# SensorBreakout.net
KiCad netlist of a schematic drawn in Altium Designer
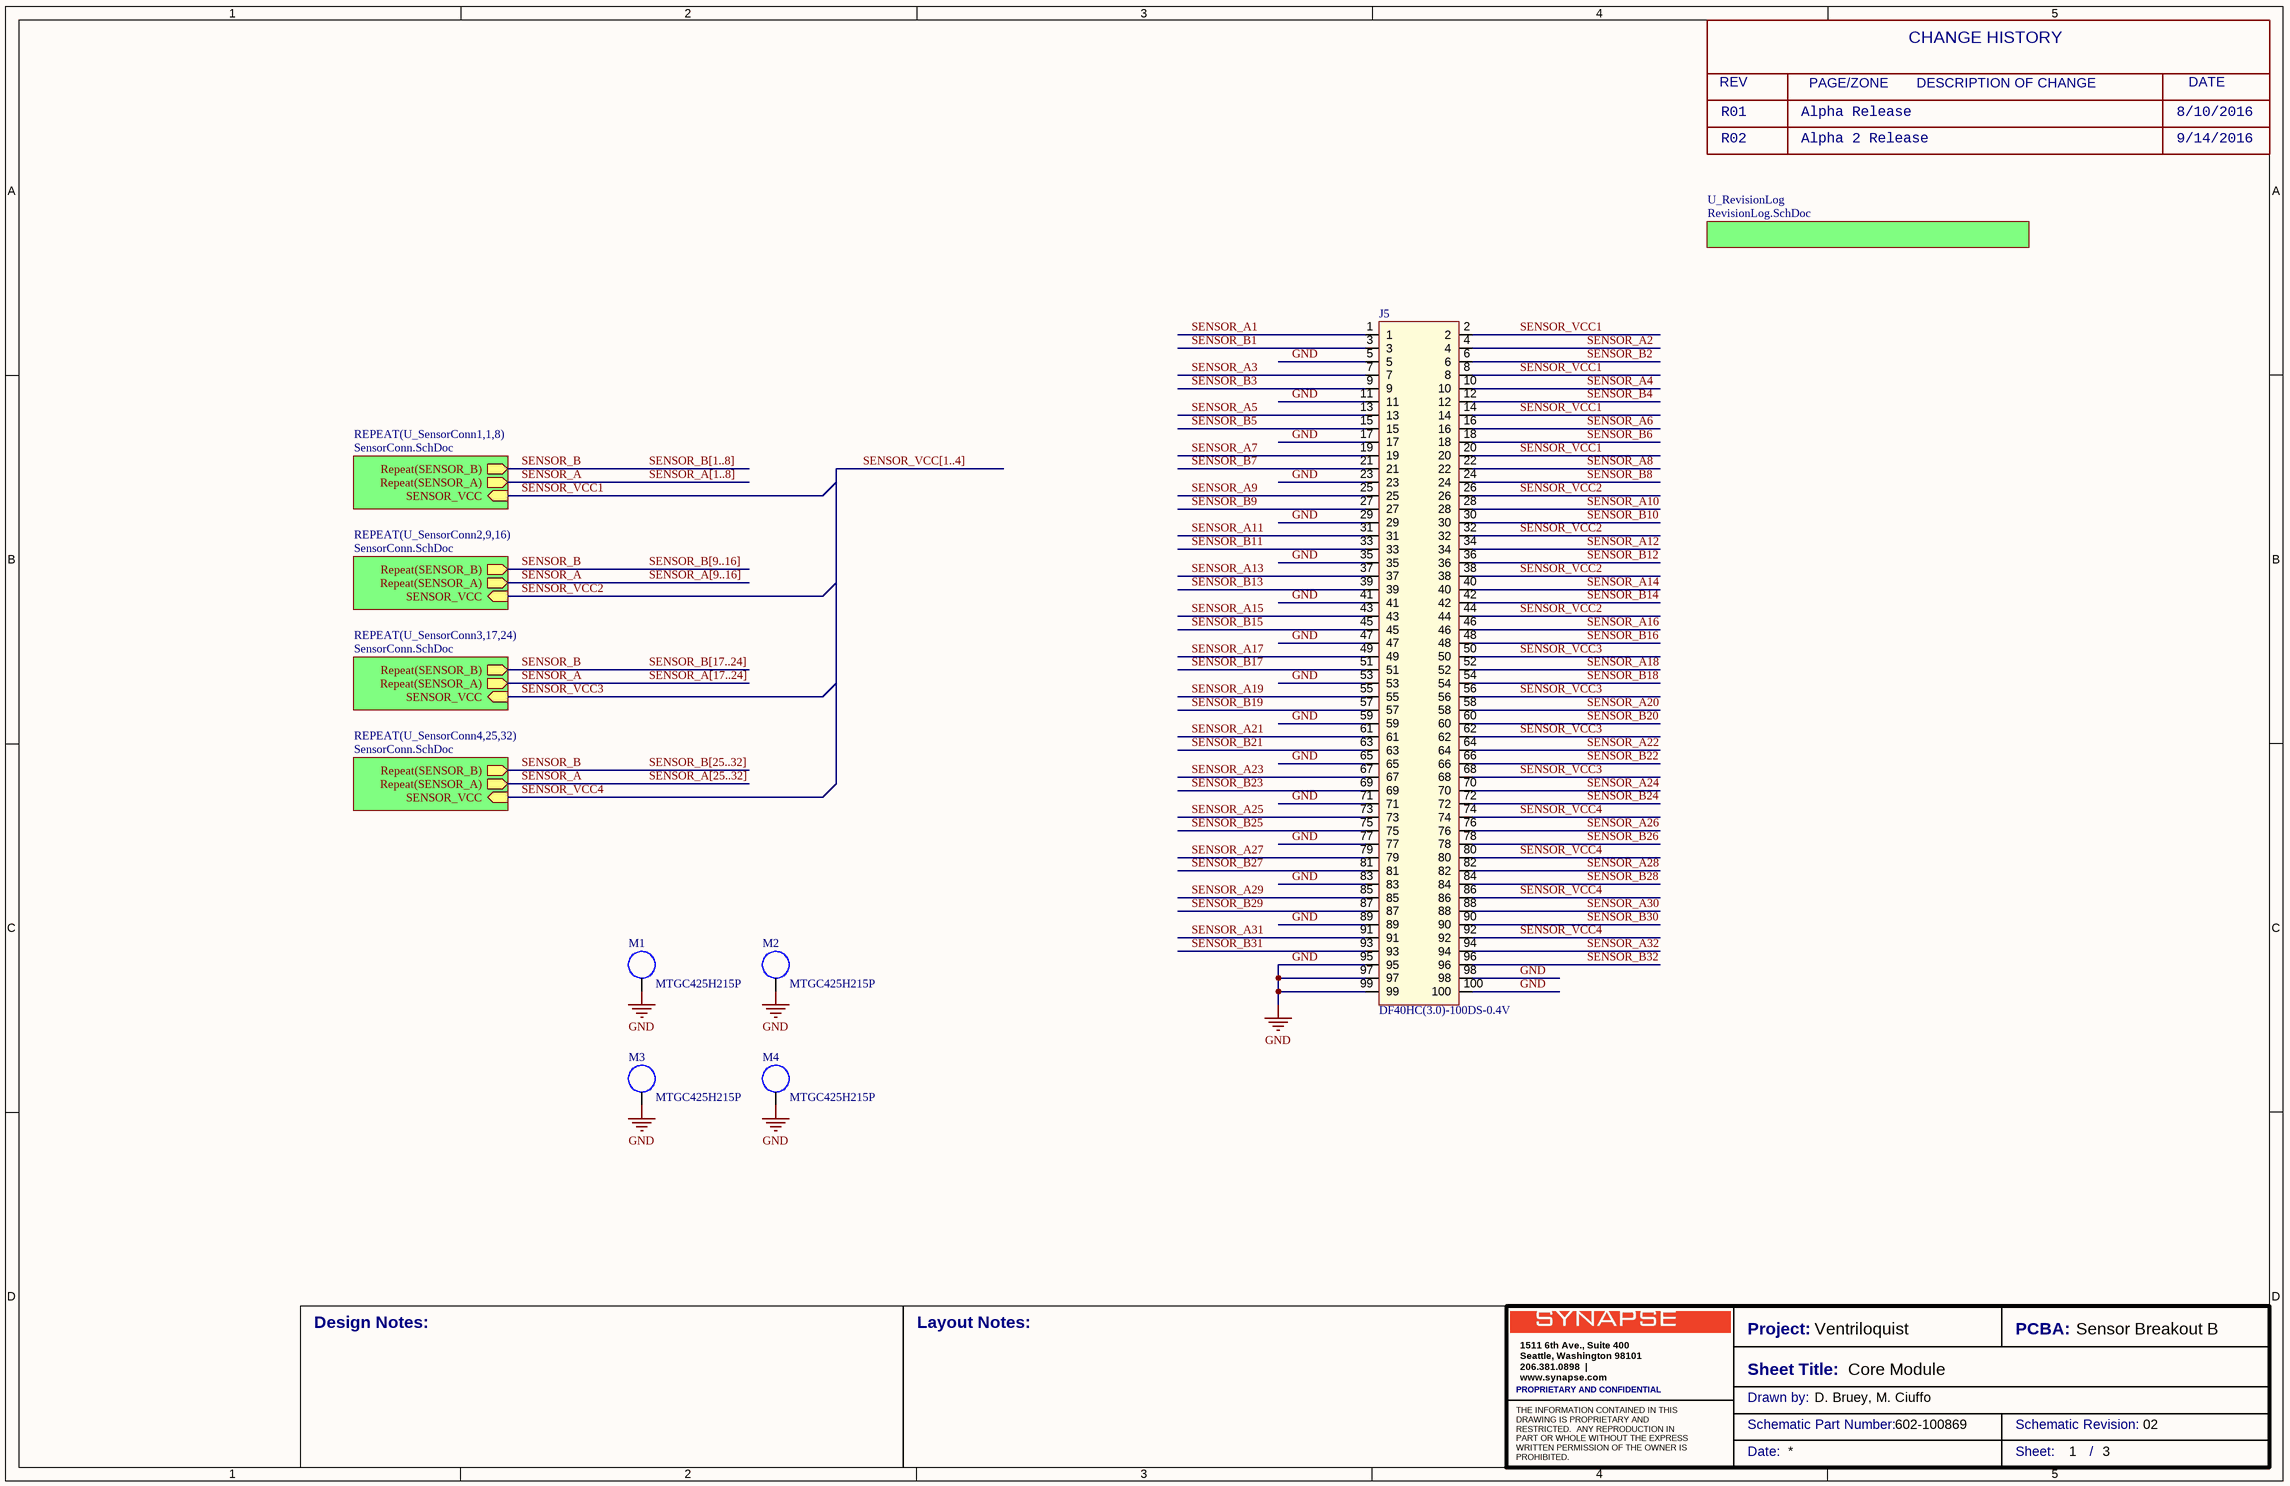
[diagram p0: SensorBreakout.SchDoc]

(export (version "E")
  (design (tool "Eeschema 10.0.6"))
  (components
    (comp (ref "J5")
      (value "DF40HC(3.0)-100DS-0.4V")
      (footprint "con100_hirose-df40c-100ds_129h")
      (description "CONN RCPT 100POS 0.4MM SMD GOLD 3.0MM")
      (fields (field (name "MFG") "Hirose") (field (name "VOLTAGE") "30V"))
      (libsource (lib "SynapseLibrary") (part "DF40C-100DS-0.4(51)"))
    )
    (comp (ref "M1")
      (value "MTGC425H215P")
      (footprint "MTGC425H215P")
      (description "MTG, 4.25mm PAD, 2.15mm Plated Hole")
      (libsource (lib "SynapseLibrary") (part "MTG"))
    )
    (comp (ref "M2")
      (value "MTGC425H215P")
      (footprint "MTGC425H215P")
      (description "MTG, 4.25mm PAD, 2.15mm Plated Hole")
      (libsource (lib "SynapseLibrary") (part "MTG"))
    )
    (comp (ref "M3")
      (value "MTGC425H215P")
      (footprint "MTGC425H215P")
      (description "MTG, 4.25mm PAD, 2.15mm Plated Hole")
      (libsource (lib "SynapseLibrary") (part "MTG"))
    )
    (comp (ref "M4")
      (value "MTGC425H215P")
      (footprint "MTGC425H215P")
      (description "MTG, 4.25mm PAD, 2.15mm Plated Hole")
      (libsource (lib "SynapseLibrary") (part "MTG"))
    )
  )
  (nets
    (net (code "2") (name "/SENSOR_A1") (class "Default")
      (node (ref "J5") (pin "1") (pinfunction "1_1") (pintype "passive"))
    )
    (net (code "3") (name "/SENSOR_A2") (class "Default")
      (node (ref "J5") (pin "4") (pinfunction "4_4") (pintype "passive"))
    )
    (net (code "4") (name "/SENSOR_A3") (class "Default")
      (node (ref "J5") (pin "7") (pinfunction "7_7") (pintype "passive"))
    )
    (net (code "5") (name "/SENSOR_A4") (class "Default")
      (node (ref "J5") (pin "10") (pinfunction "10_10") (pintype "passive"))
    )
    (net (code "6") (name "/SENSOR_A5") (class "Default")
      (node (ref "J5") (pin "13") (pinfunction "13_13") (pintype "passive"))
    )
    (net (code "7") (name "/SENSOR_A6") (class "Default")
      (node (ref "J5") (pin "16") (pinfunction "16_16") (pintype "passive"))
    )
    (net (code "8") (name "/SENSOR_A7") (class "Default")
      (node (ref "J5") (pin "19") (pinfunction "19_19") (pintype "passive"))
    )
    (net (code "9") (name "/SENSOR_A8") (class "Default")
      (node (ref "J5") (pin "22") (pinfunction "22_22") (pintype "passive"))
    )
    (net (code "10") (name "/SENSOR_A9") (class "Default")
      (node (ref "J5") (pin "25") (pinfunction "25_25") (pintype "passive"))
    )
    (net (code "11") (name "/SENSOR_A10") (class "Default")
      (node (ref "J5") (pin "28") (pinfunction "28_28") (pintype "passive"))
    )
    (net (code "12") (name "/SENSOR_A11") (class "Default")
      (node (ref "J5") (pin "31") (pinfunction "31_31") (pintype "passive"))
    )
    (net (code "13") (name "/SENSOR_A12") (class "Default")
      (node (ref "J5") (pin "34") (pinfunction "34_34") (pintype "passive"))
    )
    (net (code "14") (name "/SENSOR_A13") (class "Default")
      (node (ref "J5") (pin "37") (pinfunction "37_37") (pintype "passive"))
    )
    (net (code "15") (name "/SENSOR_A14") (class "Default")
      (node (ref "J5") (pin "40") (pinfunction "40_40") (pintype "passive"))
    )
    (net (code "16") (name "/SENSOR_A15") (class "Default")
      (node (ref "J5") (pin "43") (pinfunction "43_43") (pintype "passive"))
    )
    (net (code "17") (name "/SENSOR_A16") (class "Default")
      (node (ref "J5") (pin "46") (pinfunction "46_46") (pintype "passive"))
    )
    (net (code "18") (name "/SENSOR_A17") (class "Default")
      (node (ref "J5") (pin "49") (pinfunction "49_49") (pintype "passive"))
    )
    (net (code "19") (name "/SENSOR_A18") (class "Default")
      (node (ref "J5") (pin "52") (pinfunction "52_52") (pintype "passive"))
    )
    (net (code "20") (name "/SENSOR_A19") (class "Default")
      (node (ref "J5") (pin "55") (pinfunction "55_55") (pintype "passive"))
    )
    (net (code "21") (name "/SENSOR_A20") (class "Default")
      (node (ref "J5") (pin "58") (pinfunction "58_58") (pintype "passive"))
    )
    (net (code "22") (name "/SENSOR_A21") (class "Default")
      (node (ref "J5") (pin "61") (pinfunction "61_61") (pintype "passive"))
    )
    (net (code "23") (name "/SENSOR_A22") (class "Default")
      (node (ref "J5") (pin "64") (pinfunction "64_64") (pintype "passive"))
    )
    (net (code "24") (name "/SENSOR_A23") (class "Default")
      (node (ref "J5") (pin "67") (pinfunction "67_67") (pintype "passive"))
    )
    (net (code "25") (name "/SENSOR_A24") (class "Default")
      (node (ref "J5") (pin "70") (pinfunction "70_70") (pintype "passive"))
    )
    (net (code "26") (name "/SENSOR_A25") (class "Default")
      (node (ref "J5") (pin "73") (pinfunction "73_73") (pintype "passive"))
    )
    (net (code "27") (name "/SENSOR_A26") (class "Default")
      (node (ref "J5") (pin "76") (pinfunction "76_76") (pintype "passive"))
    )
    (net (code "28") (name "/SENSOR_A27") (class "Default")
      (node (ref "J5") (pin "79") (pinfunction "79_79") (pintype "passive"))
    )
    (net (code "29") (name "/SENSOR_A28") (class "Default")
      (node (ref "J5") (pin "82") (pinfunction "82_82") (pintype "passive"))
    )
    (net (code "30") (name "/SENSOR_A29") (class "Default")
      (node (ref "J5") (pin "85") (pinfunction "85_85") (pintype "passive"))
    )
    (net (code "31") (name "/SENSOR_A30") (class "Default")
      (node (ref "J5") (pin "88") (pinfunction "88_88") (pintype "passive"))
    )
    (net (code "32") (name "/SENSOR_A31") (class "Default")
      (node (ref "J5") (pin "91") (pinfunction "91_91") (pintype "passive"))
    )
    (net (code "33") (name "/SENSOR_A32") (class "Default")
      (node (ref "J5") (pin "94") (pinfunction "94_94") (pintype "passive"))
    )
    (net (code "39") (name "/SENSOR_B1") (class "Default")
      (node (ref "J5") (pin "3") (pinfunction "3_3") (pintype "passive"))
    )
    (net (code "40") (name "/SENSOR_B2") (class "Default")
      (node (ref "J5") (pin "6") (pinfunction "6_6") (pintype "passive"))
    )
    (net (code "41") (name "/SENSOR_B3") (class "Default")
      (node (ref "J5") (pin "9") (pinfunction "9_9") (pintype "passive"))
    )
    (net (code "42") (name "/SENSOR_B4") (class "Default")
      (node (ref "J5") (pin "12") (pinfunction "12_12") (pintype "passive"))
    )
    (net (code "43") (name "/SENSOR_B5") (class "Default")
      (node (ref "J5") (pin "15") (pinfunction "15_15") (pintype "passive"))
    )
    (net (code "44") (name "/SENSOR_B6") (class "Default")
      (node (ref "J5") (pin "18") (pinfunction "18_18") (pintype "passive"))
    )
    (net (code "45") (name "/SENSOR_B7") (class "Default")
      (node (ref "J5") (pin "21") (pinfunction "21_21") (pintype "passive"))
    )
    (net (code "46") (name "/SENSOR_B8") (class "Default")
      (node (ref "J5") (pin "24") (pinfunction "24_24") (pintype "passive"))
    )
    (net (code "47") (name "/SENSOR_B9") (class "Default")
      (node (ref "J5") (pin "27") (pinfunction "27_27") (pintype "passive"))
    )
    (net (code "48") (name "/SENSOR_B10") (class "Default")
      (node (ref "J5") (pin "30") (pinfunction "30_30") (pintype "passive"))
    )
    (net (code "49") (name "/SENSOR_B11") (class "Default")
      (node (ref "J5") (pin "33") (pinfunction "33_33") (pintype "passive"))
    )
    (net (code "50") (name "/SENSOR_B12") (class "Default")
      (node (ref "J5") (pin "36") (pinfunction "36_36") (pintype "passive"))
    )
    (net (code "51") (name "/SENSOR_B13") (class "Default")
      (node (ref "J5") (pin "39") (pinfunction "39_39") (pintype "passive"))
    )
    (net (code "52") (name "/SENSOR_B14") (class "Default")
      (node (ref "J5") (pin "42") (pinfunction "42_42") (pintype "passive"))
    )
    (net (code "53") (name "/SENSOR_B15") (class "Default")
      (node (ref "J5") (pin "45") (pinfunction "45_45") (pintype "passive"))
    )
    (net (code "54") (name "/SENSOR_B16") (class "Default")
      (node (ref "J5") (pin "48") (pinfunction "48_48") (pintype "passive"))
    )
    (net (code "55") (name "/SENSOR_B17") (class "Default")
      (node (ref "J5") (pin "51") (pinfunction "51_51") (pintype "passive"))
    )
    (net (code "56") (name "/SENSOR_B18") (class "Default")
      (node (ref "J5") (pin "54") (pinfunction "54_54") (pintype "passive"))
    )
    (net (code "57") (name "/SENSOR_B19") (class "Default")
      (node (ref "J5") (pin "57") (pinfunction "57_57") (pintype "passive"))
    )
    (net (code "58") (name "/SENSOR_B20") (class "Default")
      (node (ref "J5") (pin "60") (pinfunction "60_60") (pintype "passive"))
    )
    (net (code "59") (name "/SENSOR_B21") (class "Default")
      (node (ref "J5") (pin "63") (pinfunction "63_63") (pintype "passive"))
    )
    (net (code "60") (name "/SENSOR_B22") (class "Default")
      (node (ref "J5") (pin "66") (pinfunction "66_66") (pintype "passive"))
    )
    (net (code "61") (name "/SENSOR_B23") (class "Default")
      (node (ref "J5") (pin "69") (pinfunction "69_69") (pintype "passive"))
    )
    (net (code "62") (name "/SENSOR_B24") (class "Default")
      (node (ref "J5") (pin "72") (pinfunction "72_72") (pintype "passive"))
    )
    (net (code "63") (name "/SENSOR_B25") (class "Default")
      (node (ref "J5") (pin "75") (pinfunction "75_75") (pintype "passive"))
    )
    (net (code "64") (name "/SENSOR_B26") (class "Default")
      (node (ref "J5") (pin "78") (pinfunction "78_78") (pintype "passive"))
    )
    (net (code "65") (name "/SENSOR_B27") (class "Default")
      (node (ref "J5") (pin "81") (pinfunction "81_81") (pintype "passive"))
    )
    (net (code "66") (name "/SENSOR_B28") (class "Default")
      (node (ref "J5") (pin "84") (pinfunction "84_84") (pintype "passive"))
    )
    (net (code "67") (name "/SENSOR_B29") (class "Default")
      (node (ref "J5") (pin "87") (pinfunction "87_87") (pintype "passive"))
    )
    (net (code "68") (name "/SENSOR_B30") (class "Default")
      (node (ref "J5") (pin "90") (pinfunction "90_90") (pintype "passive"))
    )
    (net (code "69") (name "/SENSOR_B31") (class "Default")
      (node (ref "J5") (pin "93") (pinfunction "93_93") (pintype "passive"))
    )
    (net (code "70") (name "/SENSOR_B32") (class "Default")
      (node (ref "J5") (pin "96") (pinfunction "96_96") (pintype "passive"))
    )
    (net (code "75") (name "/SENSOR_VCC1") (class "Default")
      (node (ref "J5") (pin "14") (pinfunction "14_14") (pintype "passive"))
      (node (ref "J5") (pin "2") (pinfunction "2_2") (pintype "passive"))
      (node (ref "J5") (pin "20") (pinfunction "20_20") (pintype "passive"))
      (node (ref "J5") (pin "8") (pinfunction "8_8") (pintype "passive"))
    )
    (net (code "76") (name "/SENSOR_VCC2") (class "Default")
      (node (ref "J5") (pin "26") (pinfunction "26_26") (pintype "passive"))
      (node (ref "J5") (pin "32") (pinfunction "32_32") (pintype "passive"))
      (node (ref "J5") (pin "38") (pinfunction "38_38") (pintype "passive"))
      (node (ref "J5") (pin "44") (pinfunction "44_44") (pintype "passive"))
    )
    (net (code "77") (name "/SENSOR_VCC3") (class "Default")
      (node (ref "J5") (pin "50") (pinfunction "50_50") (pintype "passive"))
      (node (ref "J5") (pin "56") (pinfunction "56_56") (pintype "passive"))
      (node (ref "J5") (pin "62") (pinfunction "62_62") (pintype "passive"))
      (node (ref "J5") (pin "68") (pinfunction "68_68") (pintype "passive"))
    )
    (net (code "78") (name "/SENSOR_VCC4") (class "Default")
      (node (ref "J5") (pin "74") (pinfunction "74_74") (pintype "passive"))
      (node (ref "J5") (pin "80") (pinfunction "80_80") (pintype "passive"))
      (node (ref "J5") (pin "86") (pinfunction "86_86") (pintype "passive"))
      (node (ref "J5") (pin "92") (pinfunction "92_92") (pintype "passive"))
    )
    (net (code "80") (name "GND") (class "Default")
      (node (ref "J5") (pin "100") (pinfunction "100_100") (pintype "passive"))
      (node (ref "J5") (pin "11") (pinfunction "11_11") (pintype "passive"))
      (node (ref "J5") (pin "17") (pinfunction "17_17") (pintype "passive"))
      (node (ref "J5") (pin "23") (pinfunction "23_23") (pintype "passive"))
      (node (ref "J5") (pin "29") (pinfunction "29_29") (pintype "passive"))
      (node (ref "J5") (pin "35") (pinfunction "35_35") (pintype "passive"))
      (node (ref "J5") (pin "41") (pinfunction "41_41") (pintype "passive"))
      (node (ref "J5") (pin "47") (pinfunction "47_47") (pintype "passive"))
      (node (ref "J5") (pin "5") (pinfunction "5_5") (pintype "passive"))
      (node (ref "J5") (pin "53") (pinfunction "53_53") (pintype "passive"))
      (node (ref "J5") (pin "59") (pinfunction "59_59") (pintype "passive"))
      (node (ref "J5") (pin "65") (pinfunction "65_65") (pintype "passive"))
      (node (ref "J5") (pin "71") (pinfunction "71_71") (pintype "passive"))
      (node (ref "J5") (pin "77") (pinfunction "77_77") (pintype "passive"))
      (node (ref "J5") (pin "83") (pinfunction "83_83") (pintype "passive"))
      (node (ref "J5") (pin "89") (pinfunction "89_89") (pintype "passive"))
      (node (ref "J5") (pin "95") (pinfunction "95_95") (pintype "passive"))
      (node (ref "J5") (pin "97") (pinfunction "97_97") (pintype "passive"))
      (node (ref "J5") (pin "98") (pinfunction "98_98") (pintype "passive"))
      (node (ref "J5") (pin "99") (pinfunction "99_99") (pintype "passive"))
      (node (ref "M1") (pin "1") (pinfunction "1_1") (pintype "passive"))
      (node (ref "M2") (pin "1") (pinfunction "1_1") (pintype "passive"))
      (node (ref "M3") (pin "1") (pinfunction "1_1") (pintype "passive"))
      (node (ref "M4") (pin "1") (pinfunction "1_1") (pintype "passive"))
    )
  )
)
